# 16_-CLOCK.net
KiCad netlist of a schematic drawn in Altium Designer
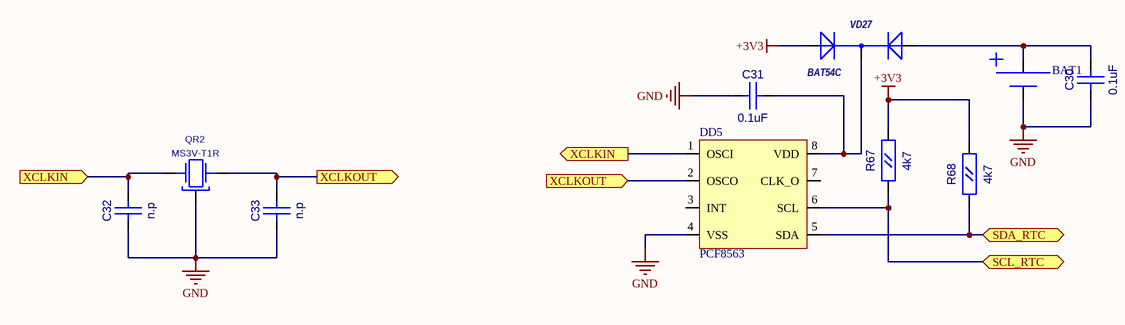
[diagram p0: [16]-CLOCK.SchDoc]

(export (version "E")
  (design (tool "Eeschema 10.0.6"))
  (components
    (comp (ref "BAT1")
      (value "CR2032-VBY4")
      (footprint "CR2032_ONBOARD")
      (libsource (lib "fizik_lib") (part "CR2032-VBY2"))
    )
    (comp (ref "C30")
      (value "0.1uF")
      (footprint "CC0603")
      (description "CC0603")
      (libsource (lib "gprs_modem_2") (part "CC0603"))
    )
    (comp (ref "C31")
      (value "0.1uF")
      (footprint "CC0603")
      (description "CC0603")
      (libsource (lib "gprs_modem_2") (part "CC0603"))
    )
    (comp (ref "C32")
      (value "n.p")
      (footprint "CC0603")
      (description "CC0603")
      (libsource (lib "gprs_modem_2") (part "CC0603"))
    )
    (comp (ref "C33")
      (value "n.p")
      (footprint "CC0603")
      (description "CC0603")
      (libsource (lib "gprs_modem_2") (part "CC0603"))
    )
    (comp (ref "DD5") (value "PCF8563") (footprint "SO-8") (libsource (lib "gprs_modem") (part "PCF8563")))
    (comp (ref "QR2")
      (value "MS3V-T1R")
      (footprint "MS3V-T1R")
      (description "CRYSTAL_32768 Hz")
      (libsource (lib "gprs_modem") (part "MS3V-T1R"))
    )
    (comp (ref "R67")
      (value "4k7")
      (footprint "RC0603")
      (description "RC0603")
      (libsource (lib "gprs_modem_2") (part "RC0603"))
    )
    (comp (ref "R68")
      (value "4k7")
      (footprint "RC0603")
      (description "RC0603")
      (libsource (lib "gprs_modem_2") (part "RC0603"))
    )
    (comp (ref "VD27")
      (value "BAT54C")
      (footprint "SOT-23(123)")
      (libsource (lib "gprs_modem_2") (part "BAT54C"))
    )
  )
  (nets
    (net (code "1") (name "+3V3") (class "Default")
      (node (ref "R67") (pin "2") (pinfunction "B_2") (pintype "passive"))
      (node (ref "R68") (pin "2") (pinfunction "B_2") (pintype "passive"))
      (node (ref "VD27") (pin "1") (pinfunction "A_1") (pintype "passive"))
    )
    (net (code "2") (name "/SCL_RTC") (class "Default")
      (node (ref "DD5") (pin "6") (pinfunction "SCL_6") (pintype "passive"))
      (node (ref "R67") (pin "1") (pinfunction "A_1") (pintype "passive"))
    )
    (net (code "3") (name "/SDA_RTC") (class "Default")
      (node (ref "DD5") (pin "5") (pinfunction "SDA_5") (pintype "passive"))
      (node (ref "R68") (pin "1") (pinfunction "A_1") (pintype "passive"))
    )
    (net (code "4") (name "/XCLKIN") (class "Default")
      (node (ref "C32") (pin "2") (pinfunction "B_2") (pintype "passive"))
      (node (ref "DD5") (pin "1") (pinfunction "OSCI_1") (pintype "passive"))
      (node (ref "QR2") (pin "2") (pinfunction "X2_2") (pintype "passive"))
    )
    (net (code "5") (name "/XCLKOUT") (class "Default")
      (node (ref "C33") (pin "2") (pinfunction "B_2") (pintype "passive"))
      (node (ref "DD5") (pin "2") (pinfunction "OSCO_2") (pintype "passive"))
      (node (ref "QR2") (pin "1") (pinfunction "X1_1") (pintype "passive"))
    )
    (net (code "6") (name "GND") (class "Default")
      (node (ref "BAT1") (pin "1") (pintype "passive"))
      (node (ref "C30") (pin "1") (pinfunction "A_1") (pintype "passive"))
      (node (ref "C31") (pin "1") (pinfunction "A_1") (pintype "passive"))
      (node (ref "C32") (pin "1") (pinfunction "A_1") (pintype "passive"))
      (node (ref "C33") (pin "1") (pinfunction "A_1") (pintype "passive"))
      (node (ref "DD5") (pin "4") (pinfunction "VSS_4") (pintype "passive"))
      (node (ref "QR2") (pin "3") (pinfunction "3_3") (pintype "passive"))
    )
    (net (code "7") (name "Net-(C30-B)") (class "Default")
      (node (ref "BAT1") (pin "2") (pintype "passive"))
      (node (ref "C30") (pin "2") (pinfunction "B_2") (pintype "passive"))
      (node (ref "VD27") (pin "2") (pinfunction "A_2") (pintype "passive"))
    )
    (net (code "8") (name "Net-(C31-B)") (class "Default")
      (node (ref "C31") (pin "2") (pinfunction "B_2") (pintype "passive"))
      (node (ref "DD5") (pin "8") (pinfunction "VDD_8") (pintype "passive"))
      (node (ref "VD27") (pin "3") (pinfunction "K_3") (pintype "passive"))
    )
    (net (code "9") (name "unconnected-(DD5-CLK_O-Pad7)") (class "Default")
      (node (ref "DD5") (pin "7") (pinfunction "CLK_O_7") (pintype "passive"))
    )
    (net (code "10") (name "unconnected-(DD5-INT-Pad3)") (class "Default")
      (node (ref "DD5") (pin "3") (pinfunction "INT_3") (pintype "passive"))
    )
  )
)
